# SparkFun_STUSB4500_USB-PD.net
KiCad netlist of a schematic drawn in EAGLE
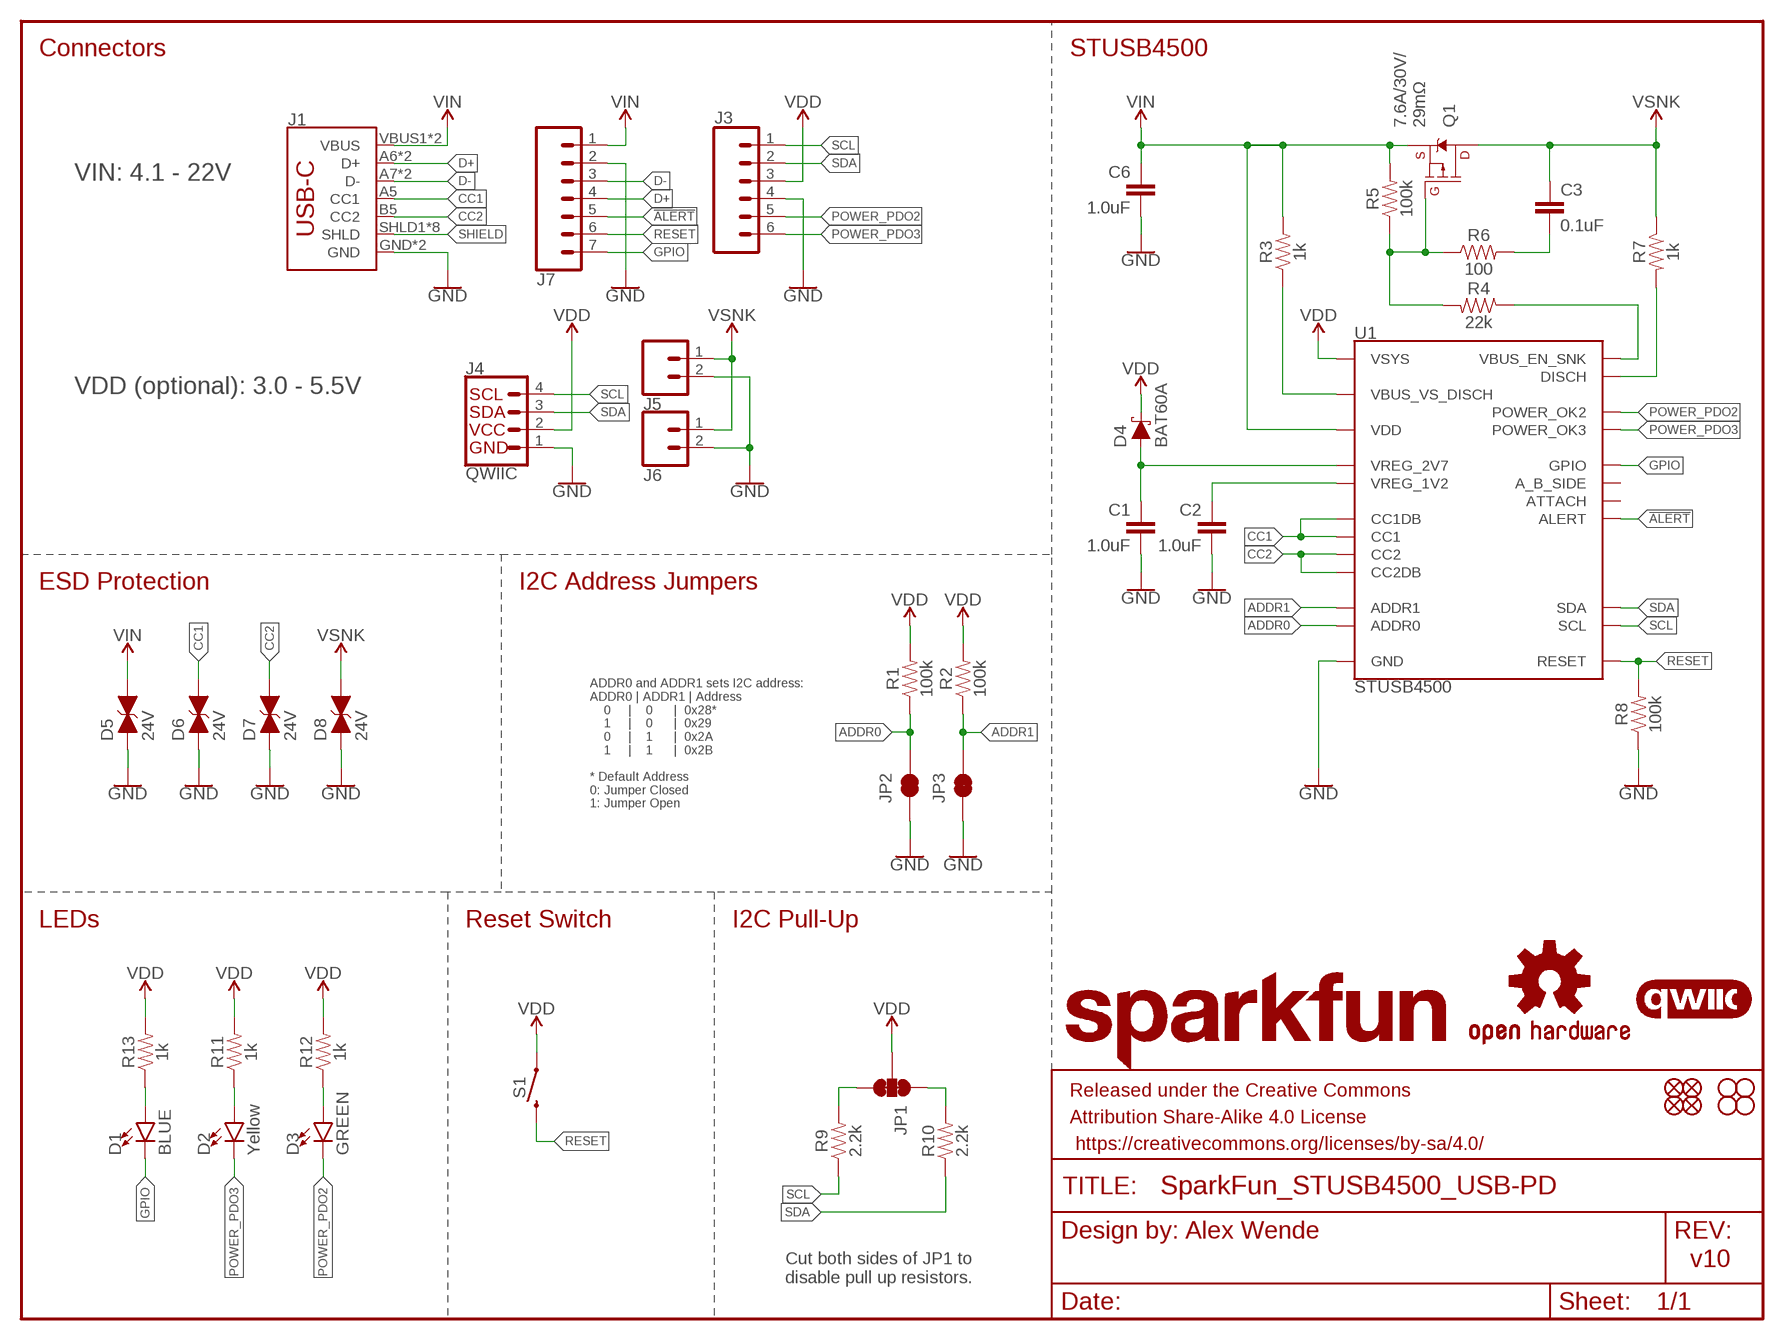
[diagram p0: schematic, sheet 1]

(export (version "E")
  (design (tool "Eeschema 10.0.6"))
  (components
    (comp (ref "C1")
      (value "1.0uF")
      (footprint "eagle-import:0603")
      (libsource (lib "eagle-import") (part "1.0UF-0603-16V-10%"))
    )
    (comp (ref "C2")
      (value "1.0uF")
      (footprint "eagle-import:0603")
      (libsource (lib "eagle-import") (part "1.0UF-0603-16V-10%"))
    )
    (comp (ref "C3")
      (value "0.1uF")
      (footprint "eagle-import:0603")
      (libsource (lib "eagle-import") (part "0.1UF-0603-100V-10%"))
    )
    (comp (ref "C6")
      (value "1.0uF")
      (footprint "eagle-import:0603")
      (libsource (lib "eagle-import") (part "1.0UF-0603-16V-10%"))
    )
    (comp (ref "D1")
      (value "BLUE")
      (footprint "eagle-import:LED-0603")
      (libsource (lib "eagle-import") (part "LED-BLUE0603"))
    )
    (comp (ref "D2")
      (value "Yellow")
      (footprint "eagle-import:LED-0603")
      (libsource (lib "eagle-import") (part "LED-YELLOW0603"))
    )
    (comp (ref "D3")
      (value "GREEN")
      (footprint "eagle-import:LED-0603")
      (libsource (lib "eagle-import") (part "LED-GREEN0603"))
    )
    (comp (ref "D4")
      (value "BAT60A")
      (footprint "eagle-import:SOD-323")
      (libsource (lib "eagle-import") (part "DIODE-SCHOTTKY-BAT60A"))
    )
    (comp (ref "D5")
      (value "24V")
      (footprint "eagle-import:0603")
      (libsource (lib "eagle-import") (part "DIODE_TVS"))
    )
    (comp (ref "D6")
      (value "24V")
      (footprint "eagle-import:0603")
      (libsource (lib "eagle-import") (part "DIODE_TVS"))
    )
    (comp (ref "D7")
      (value "24V")
      (footprint "eagle-import:0603")
      (libsource (lib "eagle-import") (part "DIODE_TVS"))
    )
    (comp (ref "D8")
      (value "24V")
      (footprint "eagle-import:0603")
      (libsource (lib "eagle-import") (part "DIODE_TVS"))
    )
    (comp (ref "FD1")
      (value "FIDUCIALUFIDUCIAL")
      (footprint "eagle-import:FIDUCIAL-MICRO")
      (libsource (lib "eagle-import") (part "FIDUCIALUFIDUCIAL"))
    )
    (comp (ref "FD2")
      (value "FIDUCIALUFIDUCIAL")
      (footprint "eagle-import:FIDUCIAL-MICRO")
      (libsource (lib "eagle-import") (part "FIDUCIALUFIDUCIAL"))
    )
    (comp (ref "FD3")
      (value "FIDUCIALUFIDUCIAL")
      (footprint "eagle-import:FIDUCIAL-MICRO")
      (libsource (lib "eagle-import") (part "FIDUCIALUFIDUCIAL"))
    )
    (comp (ref "FD4")
      (value "FIDUCIALUFIDUCIAL")
      (footprint "eagle-import:FIDUCIAL-MICRO")
      (libsource (lib "eagle-import") (part "FIDUCIALUFIDUCIAL"))
    )
    (comp (ref "FRAME1")
      (value "FRAME-LETTER")
      (footprint "eagle-import:CREATIVE_COMMONS")
      (libsource (lib "eagle-import") (part "FRAME-LETTER"))
    )
    (comp (ref "H1")
      (value "STAND-OFF")
      (footprint "eagle-import:STAND-OFF")
      (libsource (lib "eagle-import") (part "STAND-OFF"))
    )
    (comp (ref "H2")
      (value "STAND-OFF")
      (footprint "eagle-import:STAND-OFF")
      (libsource (lib "eagle-import") (part "STAND-OFF"))
    )
    (comp (ref "H3")
      (value "STAND-OFF")
      (footprint "eagle-import:STAND-OFF")
      (libsource (lib "eagle-import") (part "STAND-OFF"))
    )
    (comp (ref "H4")
      (value "STAND-OFF")
      (footprint "eagle-import:STAND-OFF")
      (libsource (lib "eagle-import") (part "STAND-OFF"))
    )
    (comp (ref "J1")
      (value "USB_C2-LAYER")
      (footprint "eagle-import:USB-C-16P")
      (libsource (lib "eagle-import") (part "USB_C2-LAYER"))
    )
    (comp (ref "J3")
      (value "CONN_06NO_SILK_NO_POP")
      (footprint "eagle-import:1X06_NO_SILK")
      (libsource (lib "eagle-import") (part "CONN_06NO_SILK_NO_POP"))
    )
    (comp (ref "J4")
      (value "QWIIC")
      (footprint "eagle-import:JST04_1MM_RA")
      (libsource (lib "eagle-import") (part "QWIIC_CONNECTORJS-1MM"))
    )
    (comp (ref "J5")
      (value "CONN_023.5MM")
      (footprint "eagle-import:SCREWTERMINAL-3.5MM-2")
      (libsource (lib "eagle-import") (part "CONN_023.5MM"))
    )
    (comp (ref "J6")
      (value "CONN_021X02_NO_SILK")
      (footprint "eagle-import:1X02_NO_SILK")
      (libsource (lib "eagle-import") (part "CONN_021X02_NO_SILK"))
    )
    (comp (ref "J7")
      (value "CONN_07NO_SILK")
      (footprint "eagle-import:1X07_NO_SILK")
      (libsource (lib "eagle-import") (part "CONN_07NO_SILK"))
    )
    (comp (ref "JP1")
      (value "JUMPER-SMT_3_2-NC_TRACE_NO-SILK")
      (footprint "eagle-import:SMT-JUMPER_3_2-NC_TRACE_NO-SILK")
      (libsource (lib "eagle-import") (part "JUMPER-SMT_3_2-NC_TRACE_NO-SILK"))
    )
    (comp (ref "JP2")
      (value "JUMPER-SMT_2_NC_TRACE_NO-SILK")
      (footprint "eagle-import:SMT-JUMPER_2_NC_TRACE_NO-SILK")
      (libsource (lib "eagle-import") (part "JUMPER-SMT_2_NC_TRACE_NO-SILK"))
    )
    (comp (ref "JP3")
      (value "JUMPER-SMT_2_NC_TRACE_NO-SILK")
      (footprint "eagle-import:SMT-JUMPER_2_NC_TRACE_NO-SILK")
      (libsource (lib "eagle-import") (part "JUMPER-SMT_2_NC_TRACE_NO-SILK"))
    )
    (comp (ref "LOGO1")
      (value "OSHW-LOGOS")
      (footprint "eagle-import:OSHW-LOGO-S")
      (libsource (lib "eagle-import") (part "OSHW-LOGOS"))
    )
    (comp (ref "LOGO2")
      (value "SFE_LOGO_NAME.1_INCH")
      (footprint "eagle-import:SFE_LOGO_NAME_.1")
      (libsource (lib "eagle-import") (part "SFE_LOGO_NAME.1_INCH"))
    )
    (comp (ref "LOGO3")
      (value "QWIIC_LOGO_5MM")
      (footprint "eagle-import:QWIIC_5MM")
      (libsource (lib "eagle-import") (part "QWIIC_LOGO_5MM"))
    )
    (comp (ref "Q1")
      (value "9A/30V/15mΩ")
      (footprint "eagle-import:8-POWERVDFN-3X3")
      (libsource (lib "eagle-import") (part "MOSFET_PCH-STL9P3LLH6"))
    )
    (comp (ref "R1")
      (value "100k")
      (footprint "eagle-import:0603")
      (libsource (lib "eagle-import") (part "100KOHM-0603-1/10W-1%"))
    )
    (comp (ref "R2")
      (value "100k")
      (footprint "eagle-import:0603")
      (libsource (lib "eagle-import") (part "100KOHM-0603-1/10W-1%"))
    )
    (comp (ref "R3")
      (value "1k")
      (footprint "eagle-import:0603")
      (libsource (lib "eagle-import") (part "1KOHM-0603-1/10W-1%"))
    )
    (comp (ref "R4")
      (value "22k")
      (footprint "eagle-import:0603")
      (libsource (lib "eagle-import") (part "22KOHM-0603-1/10W-1%"))
    )
    (comp (ref "R5")
      (value "100k")
      (footprint "eagle-import:0603")
      (libsource (lib "eagle-import") (part "100KOHM-0603-1/10W-1%"))
    )
    (comp (ref "R6")
      (value "100")
      (footprint "eagle-import:0603")
      (libsource (lib "eagle-import") (part "100OHM-0603-1/10W-1%"))
    )
    (comp (ref "R7")
      (value "1k")
      (footprint "eagle-import:0603")
      (libsource (lib "eagle-import") (part "1KOHM-0603-1/10W-1%"))
    )
    (comp (ref "R8")
      (value "100k")
      (footprint "eagle-import:0603")
      (libsource (lib "eagle-import") (part "100KOHM-0603-1/10W-1%"))
    )
    (comp (ref "R9")
      (value "2.2k")
      (footprint "eagle-import:0603")
      (libsource (lib "eagle-import") (part "2.2KOHM-0603-1/10W-1%"))
    )
    (comp (ref "R10")
      (value "2.2k")
      (footprint "eagle-import:0603")
      (libsource (lib "eagle-import") (part "2.2KOHM-0603-1/10W-1%"))
    )
    (comp (ref "R11")
      (value "1k")
      (footprint "eagle-import:0603")
      (libsource (lib "eagle-import") (part "1KOHM-0603-1/10W-1%"))
    )
    (comp (ref "R12")
      (value "1k")
      (footprint "eagle-import:0603")
      (libsource (lib "eagle-import") (part "1KOHM-0603-1/10W-1%"))
    )
    (comp (ref "R13")
      (value "1k")
      (footprint "eagle-import:0603")
      (libsource (lib "eagle-import") (part "1KOHM-0603-1/10W-1%"))
    )
    (comp (ref "S1")
      (value "MOMENTARY-SWITCH-SPST-SMD-4.6X2.8MM")
      (footprint "eagle-import:TACTILE_SWITCH_SMD_4.6X2.8MM")
      (libsource (lib "eagle-import") (part "MOMENTARY-SWITCH-SPST-SMD-4.6X2.8MM"))
    )
    (comp (ref "U1")
      (value "STUSB4500")
      (footprint "eagle-import:QFN-24")
      (libsource (lib "eagle-import") (part "STUSB4500"))
    )
  )
  (nets
    (net (code "1") (name "/~{ALERT}") (class "Default")
      (node (ref "J7") (pin "5") (pinfunction "5_5") (pintype "passive"))
      (node (ref "U1") (pin "P$19") (pinfunction "ALERT_P$19") (pintype "bidirectional"))
    )
    (net (code "2") (name "ADDR0") (class "Default")
      (node (ref "JP2") (pin "2") (pinfunction "2_2") (pintype "passive"))
      (node (ref "R1") (pin "1") (pinfunction "1_1") (pintype "passive"))
      (node (ref "U1") (pin "P$12") (pinfunction "ADDR0_P$12") (pintype "bidirectional"))
    )
    (net (code "3") (name "ADDR1") (class "Default")
      (node (ref "JP3") (pin "2") (pinfunction "2_2") (pintype "passive"))
      (node (ref "R2") (pin "1") (pinfunction "1_1") (pintype "passive"))
      (node (ref "U1") (pin "P$13") (pinfunction "ADDR1_P$13") (pintype "bidirectional"))
    )
    (net (code "4") (name "CC1") (class "Default")
      (node (ref "D6") (pin "2") (pinfunction "C_2") (pintype "passive"))
      (node (ref "J1") (pin "A5") (pinfunction "CC1_A5") (pintype "bidirectional"))
      (node (ref "U1") (pin "P$1") (pinfunction "CC1DB_P$1") (pintype "bidirectional"))
      (node (ref "U1") (pin "P$2") (pinfunction "CC1_P$2") (pintype "bidirectional"))
    )
    (net (code "5") (name "CC2") (class "Default")
      (node (ref "D7") (pin "2") (pinfunction "C_2") (pintype "passive"))
      (node (ref "J1") (pin "B5") (pinfunction "CC2_B5") (pintype "bidirectional"))
      (node (ref "U1") (pin "P$4") (pinfunction "CC2_P$4") (pintype "bidirectional"))
      (node (ref "U1") (pin "P$5") (pinfunction "CC2DB_P$5") (pintype "bidirectional"))
    )
    (net (code "6") (name "D+") (class "Default")
      (node (ref "J1") (pin "A6") (pinfunction "D+_A6") (pintype "bidirectional"))
      (node (ref "J1") (pin "B6") (pinfunction "D+_B6") (pintype "bidirectional"))
      (node (ref "J7") (pin "4") (pinfunction "4_4") (pintype "passive"))
    )
    (net (code "7") (name "D-") (class "Default")
      (node (ref "J1") (pin "A7") (pinfunction "D-_A7") (pintype "bidirectional"))
      (node (ref "J1") (pin "B7") (pinfunction "D-_B7") (pintype "bidirectional"))
      (node (ref "J7") (pin "3") (pinfunction "3_3") (pintype "passive"))
    )
    (net (code "8") (name "GND") (class "Default")
      (node (ref "C1") (pin "2") (pinfunction "2_2") (pintype "passive"))
      (node (ref "C2") (pin "2") (pinfunction "2_2") (pintype "passive"))
      (node (ref "C6") (pin "2") (pinfunction "2_2") (pintype "passive"))
      (node (ref "D5") (pin "1") (pinfunction "A_1") (pintype "passive"))
      (node (ref "D6") (pin "1") (pinfunction "A_1") (pintype "passive"))
      (node (ref "D7") (pin "1") (pinfunction "A_1") (pintype "passive"))
      (node (ref "D8") (pin "1") (pinfunction "A_1") (pintype "passive"))
      (node (ref "J1") (pin "GND") (pinfunction "GND_GND") (pintype "bidirectional"))
      (node (ref "J1") (pin "GND2") (pinfunction "GND_GND2") (pintype "bidirectional"))
      (node (ref "J3") (pin "4") (pinfunction "4_4") (pintype "passive"))
      (node (ref "J4") (pin "1") (pinfunction "1_1") (pintype "power_in"))
      (node (ref "J5") (pin "2") (pinfunction "2_2") (pintype "passive"))
      (node (ref "J6") (pin "2") (pinfunction "2_2") (pintype "passive"))
      (node (ref "J7") (pin "2") (pinfunction "2_2") (pintype "passive"))
      (node (ref "JP2") (pin "1") (pinfunction "1_1") (pintype "passive"))
      (node (ref "JP3") (pin "1") (pinfunction "1_1") (pintype "passive"))
      (node (ref "R8") (pin "1") (pinfunction "1_1") (pintype "passive"))
      (node (ref "U1") (pin "P$10") (pinfunction "GND_P$10") (pintype "bidirectional"))
      (node (ref "U1") (pin "P$25") (pinfunction "GND_P$25") (pintype "bidirectional"))
    )
    (net (code "9") (name "GPIO") (class "Default")
      (node (ref "D1") (pin "C") (pinfunction "C_C") (pintype "passive"))
      (node (ref "J7") (pin "7") (pinfunction "7_7") (pintype "passive"))
      (node (ref "U1") (pin "P$15") (pinfunction "GPIO_P$15") (pintype "bidirectional"))
    )
    (net (code "10") (name "Net-(C3-Pad2)") (class "Default")
      (node (ref "C3") (pin "2") (pinfunction "2_2") (pintype "passive"))
      (node (ref "R6") (pin "2") (pinfunction "2_2") (pintype "passive"))
    )
    (net (code "11") (name "Net-(D1-PadA)") (class "Default")
      (node (ref "D1") (pin "A") (pinfunction "A_A") (pintype "passive"))
      (node (ref "R13") (pin "1") (pinfunction "1_1") (pintype "passive"))
    )
    (net (code "12") (name "Net-(D2-PadA)") (class "Default")
      (node (ref "D2") (pin "A") (pinfunction "A_A") (pintype "passive"))
      (node (ref "R11") (pin "1") (pinfunction "1_1") (pintype "passive"))
    )
    (net (code "13") (name "Net-(D3-PadA)") (class "Default")
      (node (ref "D3") (pin "A") (pinfunction "A_A") (pintype "passive"))
      (node (ref "R12") (pin "1") (pinfunction "1_1") (pintype "passive"))
    )
    (net (code "14") (name "Net-(JP1-Pad1)") (class "Default")
      (node (ref "JP1") (pin "1") (pinfunction "1_1") (pintype "passive"))
      (node (ref "R10") (pin "2") (pinfunction "2_2") (pintype "passive"))
    )
    (net (code "15") (name "Net-(JP1-Pad3)") (class "Default")
      (node (ref "JP1") (pin "3") (pinfunction "3_3") (pintype "passive"))
      (node (ref "R9") (pin "2") (pinfunction "2_2") (pintype "passive"))
    )
    (net (code "16") (name "Net-(Q1-G)") (class "Default")
      (node (ref "Q1") (pin "4") (pinfunction "G_4") (pintype "bidirectional"))
      (node (ref "R4") (pin "2") (pinfunction "2_2") (pintype "passive"))
      (node (ref "R5") (pin "1") (pinfunction "1_1") (pintype "passive"))
      (node (ref "R6") (pin "1") (pinfunction "1_1") (pintype "passive"))
    )
    (net (code "17") (name "Net-(U1-DISCH)") (class "Default")
      (node (ref "R7") (pin "2") (pinfunction "2_2") (pintype "passive"))
      (node (ref "U1") (pin "P$9") (pinfunction "DISCH_P$9") (pintype "bidirectional"))
    )
    (net (code "18") (name "Net-(U1-VBUS_EN_SNK)") (class "Default")
      (node (ref "R4") (pin "1") (pinfunction "1_1") (pintype "passive"))
      (node (ref "U1") (pin "P$16") (pinfunction "VBUS_EN_SNK_P$16") (pintype "bidirectional"))
    )
    (net (code "19") (name "Net-(U1-VBUS_VS_DISCH)") (class "Default")
      (node (ref "R3") (pin "1") (pinfunction "1_1") (pintype "passive"))
      (node (ref "U1") (pin "P$18") (pinfunction "VBUS_VS_DISCH_P$18") (pintype "bidirectional"))
    )
    (net (code "20") (name "Net-(U1-VREG_1V2)") (class "Default")
      (node (ref "C2") (pin "1") (pinfunction "1_1") (pintype "passive"))
      (node (ref "U1") (pin "P$21") (pinfunction "VREG_1V2_P$21") (pintype "bidirectional"))
    )
    (net (code "21") (name "Net-(U1-VREG_2V7)") (class "Default")
      (node (ref "C1") (pin "1") (pinfunction "1_1") (pintype "passive"))
      (node (ref "D4") (pin "A") (pinfunction "A_A") (pintype "passive"))
      (node (ref "U1") (pin "P$23") (pinfunction "VREG_2V7_P$23") (pintype "bidirectional"))
    )
    (net (code "22") (name "POWER_PDO2") (class "Default")
      (node (ref "D3") (pin "C") (pinfunction "C_C") (pintype "passive"))
      (node (ref "J3") (pin "5") (pinfunction "5_5") (pintype "passive"))
      (node (ref "U1") (pin "P$20") (pinfunction "POWER_OK2_P$20") (pintype "bidirectional"))
    )
    (net (code "23") (name "POWER_PDO3") (class "Default")
      (node (ref "D2") (pin "C") (pinfunction "C_C") (pintype "passive"))
      (node (ref "J3") (pin "6") (pinfunction "6_6") (pintype "passive"))
      (node (ref "U1") (pin "P$14") (pinfunction "POWER_OK3_P$14") (pintype "bidirectional"))
    )
    (net (code "24") (name "RESET") (class "Default")
      (node (ref "J7") (pin "6") (pinfunction "6_6") (pintype "passive"))
      (node (ref "R8") (pin "2") (pinfunction "2_2") (pintype "passive"))
      (node (ref "S1") (pin "3") (pinfunction "2_3") (pintype "passive"))
      (node (ref "S1") (pin "4") (pinfunction "2_4") (pintype "passive"))
      (node (ref "U1") (pin "P$6") (pinfunction "RESET_P$6") (pintype "bidirectional"))
    )
    (net (code "25") (name "SCL") (class "Default")
      (node (ref "J3") (pin "1") (pinfunction "1_1") (pintype "passive"))
      (node (ref "J4") (pin "4") (pinfunction "4_4") (pintype "passive"))
      (node (ref "R9") (pin "1") (pinfunction "1_1") (pintype "passive"))
      (node (ref "U1") (pin "P$7") (pinfunction "SCL_P$7") (pintype "bidirectional"))
    )
    (net (code "26") (name "SDA") (class "Default")
      (node (ref "J3") (pin "2") (pinfunction "2_2") (pintype "passive"))
      (node (ref "J4") (pin "3") (pinfunction "3_3") (pintype "passive"))
      (node (ref "R10") (pin "1") (pinfunction "1_1") (pintype "passive"))
      (node (ref "U1") (pin "P$8") (pinfunction "SDA_P$8") (pintype "bidirectional"))
    )
    (net (code "27") (name "SHIELD") (class "Default")
      (node (ref "J1") (pin "SHLD1") (pinfunction "SHLD_SHLD1") (pintype "bidirectional"))
      (node (ref "J1") (pin "SHLD2") (pinfunction "SHLD_SHLD2") (pintype "bidirectional"))
      (node (ref "J1") (pin "SHLD3") (pinfunction "SHLD_SHLD3") (pintype "bidirectional"))
      (node (ref "J1") (pin "SHLD4") (pinfunction "SHLD_SHLD4") (pintype "bidirectional"))
      (node (ref "J1") (pin "SHLD5") (pinfunction "SHLD_SHLD5") (pintype "bidirectional"))
      (node (ref "J1") (pin "SHLD6") (pinfunction "SHLD_SHLD6") (pintype "bidirectional"))
      (node (ref "J1") (pin "SHLD7") (pinfunction "SHLD_SHLD7") (pintype "bidirectional"))
      (node (ref "J1") (pin "SHLD8") (pinfunction "SHLD_SHLD8") (pintype "bidirectional"))
    )
    (net (code "28") (name "VDD") (class "Default")
      (node (ref "D4") (pin "C") (pinfunction "C_C") (pintype "passive"))
      (node (ref "J3") (pin "3") (pinfunction "3_3") (pintype "passive"))
      (node (ref "J4") (pin "2") (pinfunction "2_2") (pintype "power_in"))
      (node (ref "JP1") (pin "2") (pinfunction "2_2") (pintype "passive"))
      (node (ref "R1") (pin "2") (pinfunction "2_2") (pintype "passive"))
      (node (ref "R11") (pin "2") (pinfunction "2_2") (pintype "passive"))
      (node (ref "R12") (pin "2") (pinfunction "2_2") (pintype "passive"))
      (node (ref "R13") (pin "2") (pinfunction "2_2") (pintype "passive"))
      (node (ref "R2") (pin "2") (pinfunction "2_2") (pintype "passive"))
      (node (ref "S1") (pin "1") (pinfunction "1_1") (pintype "passive"))
      (node (ref "S1") (pin "2") (pinfunction "1_2") (pintype "passive"))
      (node (ref "U1") (pin "P$22") (pinfunction "VSYS_P$22") (pintype "bidirectional"))
    )
    (net (code "29") (name "VIN") (class "Default")
      (node (ref "C6") (pin "1") (pinfunction "1_1") (pintype "passive"))
      (node (ref "D5") (pin "2") (pinfunction "C_2") (pintype "passive"))
      (node (ref "J1") (pin "VBUS1") (pinfunction "VBUS_VBUS1") (pintype "bidirectional"))
      (node (ref "J1") (pin "VBUS2") (pinfunction "VBUS_VBUS2") (pintype "bidirectional"))
      (node (ref "J7") (pin "1") (pinfunction "1_1") (pintype "passive"))
      (node (ref "Q1") (pin "1") (pinfunction "S_1") (pintype "bidirectional"))
      (node (ref "Q1") (pin "2") (pinfunction "S_2") (pintype "bidirectional"))
      (node (ref "Q1") (pin "3") (pinfunction "S_3") (pintype "bidirectional"))
      (node (ref "R3") (pin "2") (pinfunction "2_2") (pintype "passive"))
      (node (ref "R5") (pin "2") (pinfunction "2_2") (pintype "passive"))
      (node (ref "U1") (pin "P$24") (pinfunction "VDD_P$24") (pintype "bidirectional"))
    )
    (net (code "30") (name "VSNK") (class "Default")
      (node (ref "C3") (pin "1") (pinfunction "1_1") (pintype "passive"))
      (node (ref "D8") (pin "2") (pinfunction "C_2") (pintype "passive"))
      (node (ref "J5") (pin "1") (pinfunction "1_1") (pintype "passive"))
      (node (ref "J6") (pin "1") (pinfunction "1_1") (pintype "passive"))
      (node (ref "Q1") (pin "5@1") (pinfunction "D_5@1") (pintype "bidirectional"))
      (node (ref "Q1") (pin "5@2") (pinfunction "D_5@2") (pintype "bidirectional"))
      (node (ref "Q1") (pin "5@3") (pinfunction "D_5@3") (pintype "bidirectional"))
      (node (ref "R7") (pin "1") (pinfunction "1_1") (pintype "passive"))
    )
    (net (code "31") (name "unconnected-(U1-ATTACH-PadP$11)") (class "Default")
      (node (ref "U1") (pin "P$11") (pinfunction "ATTACH_P$11") (pintype "bidirectional"))
    )
    (net (code "32") (name "unconnected-(U1-A_B_SIDE-PadP$17)") (class "Default")
      (node (ref "U1") (pin "P$17") (pinfunction "A_B_SIDE_P$17") (pintype "bidirectional"))
    )
  )
)
